# untitled.net
KiCad netlist of a schematic drawn in EAGLE
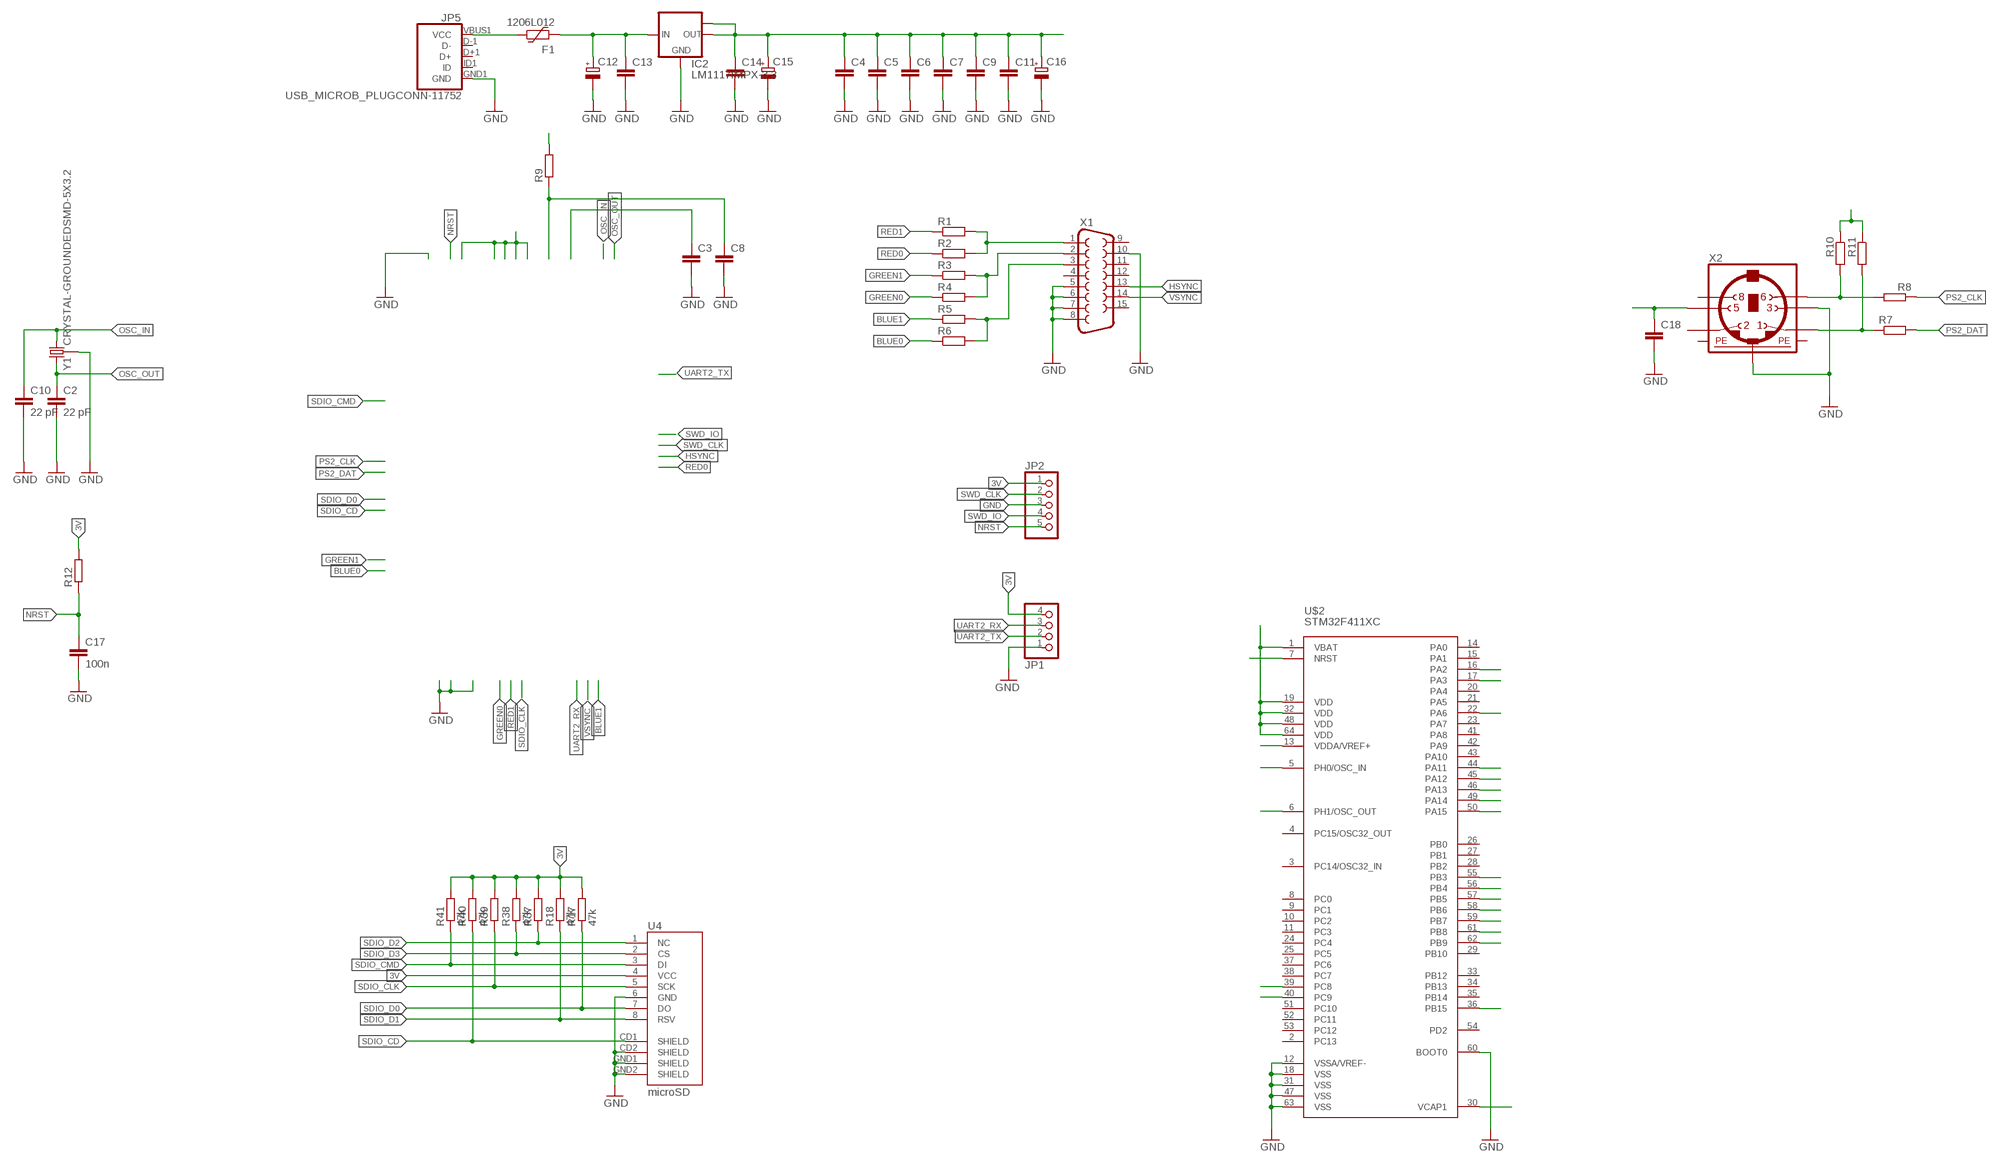
[diagram p0: schematic, sheet 1]

(export (version "E")
  (design (tool "Eeschema 10.0.6"))
  (components
    (comp (ref "C2")
      (value "22 pF")
      (footprint "eagle-import:C0603")
      (libsource (lib "eagle-import") (part "C-EUC0603"))
    )
    (comp (ref "C3")
      (value "C-EUC0603")
      (footprint "eagle-import:C0603")
      (libsource (lib "eagle-import") (part "C-EUC0603"))
    )
    (comp (ref "C4")
      (value "C-EUC0603")
      (footprint "eagle-import:C0603")
      (libsource (lib "eagle-import") (part "C-EUC0603"))
    )
    (comp (ref "C5")
      (value "C-EUC0603")
      (footprint "eagle-import:C0603")
      (libsource (lib "eagle-import") (part "C-EUC0603"))
    )
    (comp (ref "C6")
      (value "C-EUC0603")
      (footprint "eagle-import:C0603")
      (libsource (lib "eagle-import") (part "C-EUC0603"))
    )
    (comp (ref "C7")
      (value "C-EUC0603")
      (footprint "eagle-import:C0603")
      (libsource (lib "eagle-import") (part "C-EUC0603"))
    )
    (comp (ref "C8")
      (value "C-EUC0603")
      (footprint "eagle-import:C0603")
      (libsource (lib "eagle-import") (part "C-EUC0603"))
    )
    (comp (ref "C9")
      (value "C-EUC0603")
      (footprint "eagle-import:C0603")
      (libsource (lib "eagle-import") (part "C-EUC0603"))
    )
    (comp (ref "C10")
      (value "22 pF")
      (footprint "eagle-import:C0603")
      (libsource (lib "eagle-import") (part "C-EUC0603"))
    )
    (comp (ref "C11")
      (value "C-EUC0603")
      (footprint "eagle-import:C0603")
      (libsource (lib "eagle-import") (part "C-EUC0603"))
    )
    (comp (ref "C12")
      (value "CPOL-EUSMCB")
      (footprint "eagle-import:SMC_B")
      (libsource (lib "eagle-import") (part "CPOL-EUSMCB"))
    )
    (comp (ref "C13")
      (value "C-EUC0603")
      (footprint "eagle-import:C0603")
      (libsource (lib "eagle-import") (part "C-EUC0603"))
    )
    (comp (ref "C14")
      (value "C-EUC0603")
      (footprint "eagle-import:C0603")
      (libsource (lib "eagle-import") (part "C-EUC0603"))
    )
    (comp (ref "C15")
      (value "CPOL-EUSMCB")
      (footprint "eagle-import:SMC_B")
      (libsource (lib "eagle-import") (part "CPOL-EUSMCB"))
    )
    (comp (ref "C16")
      (value "CPOL-EUSMCB")
      (footprint "eagle-import:SMC_B")
      (libsource (lib "eagle-import") (part "CPOL-EUSMCB"))
    )
    (comp (ref "C17")
      (value "100n")
      (footprint "eagle-import:C0603")
      (libsource (lib "eagle-import") (part "C-EUC0603"))
    )
    (comp (ref "C18")
      (value "C-EUC0603")
      (footprint "eagle-import:C0603")
      (libsource (lib "eagle-import") (part "C-EUC0603"))
    )
    (comp (ref "F1")
      (value "1206L012")
      (footprint "eagle-import:1206L")
      (fields (field (name "MF") "Littelfuse"))
      (libsource (lib "eagle-import") (part "?1206L012"))
    )
    (comp (ref "IC2")
      (value "LM1117IMPX-3.3")
      (footprint "eagle-import:SOT223")
      (libsource (lib "eagle-import") (part "LM1117IMPX-3.3"))
    )
    (comp (ref "JP1")
      (value "PINHD-1X4")
      (footprint "eagle-import:1X04")
      (libsource (lib "eagle-import") (part "PINHD-1X4"))
    )
    (comp (ref "JP2")
      (value "PINHD-1X5")
      (footprint "eagle-import:1X05")
      (libsource (lib "eagle-import") (part "PINHD-1X5"))
    )
    (comp (ref "JP5")
      (value "USB_MICROB_PLUGCONN-11752")
      (footprint "eagle-import:USB-B-MICRO-SMD_V03")
      (libsource (lib "eagle-import") (part "USB_MICROB_PLUGCONN-11752"))
    )
    (comp (ref "R1")
      (value "R-EU_R0603")
      (footprint "eagle-import:R0603")
      (libsource (lib "eagle-import") (part "R-EU_R0603"))
    )
    (comp (ref "R2")
      (value "R-EU_R0603")
      (footprint "eagle-import:R0603")
      (libsource (lib "eagle-import") (part "R-EU_R0603"))
    )
    (comp (ref "R3")
      (value "R-EU_R0603")
      (footprint "eagle-import:R0603")
      (libsource (lib "eagle-import") (part "R-EU_R0603"))
    )
    (comp (ref "R4")
      (value "R-EU_R0603")
      (footprint "eagle-import:R0603")
      (libsource (lib "eagle-import") (part "R-EU_R0603"))
    )
    (comp (ref "R5")
      (value "R-EU_R0603")
      (footprint "eagle-import:R0603")
      (libsource (lib "eagle-import") (part "R-EU_R0603"))
    )
    (comp (ref "R6")
      (value "R-EU_R0603")
      (footprint "eagle-import:R0603")
      (libsource (lib "eagle-import") (part "R-EU_R0603"))
    )
    (comp (ref "R7")
      (value "R-EU_R0603")
      (footprint "eagle-import:R0603")
      (libsource (lib "eagle-import") (part "R-EU_R0603"))
    )
    (comp (ref "R8")
      (value "R-EU_R0603")
      (footprint "eagle-import:R0603")
      (libsource (lib "eagle-import") (part "R-EU_R0603"))
    )
    (comp (ref "R9")
      (value "R-EU_M0805")
      (footprint "eagle-import:M0805")
      (libsource (lib "eagle-import") (part "R-EU_M0805"))
    )
    (comp (ref "R10")
      (value "R-EU_R0603")
      (footprint "eagle-import:R0603")
      (libsource (lib "eagle-import") (part "R-EU_R0603"))
    )
    (comp (ref "R11")
      (value "R-EU_R0603")
      (footprint "eagle-import:R0603")
      (libsource (lib "eagle-import") (part "R-EU_R0603"))
    )
    (comp (ref "R12")
      (value "R-EU_R0603")
      (footprint "eagle-import:R0603")
      (libsource (lib "eagle-import") (part "R-EU_R0603"))
    )
    (comp (ref "R17")
      (value "47k")
      (footprint "eagle-import:R0603")
      (libsource (lib "eagle-import") (part "R-EU_R0603"))
    )
    (comp (ref "R18")
      (value "47k")
      (footprint "eagle-import:R0603")
      (libsource (lib "eagle-import") (part "R-EU_R0603"))
    )
    (comp (ref "R37")
      (value "R-EU_R0402")
      (footprint "eagle-import:R0402")
      (libsource (lib "eagle-import") (part "R-EU_R0402"))
    )
    (comp (ref "R38")
      (value "47k")
      (footprint "eagle-import:R0402")
      (libsource (lib "eagle-import") (part "R-EU_R0402"))
    )
    (comp (ref "R39")
      (value "R-EU_R0603")
      (footprint "eagle-import:R0603")
      (libsource (lib "eagle-import") (part "R-EU_R0603"))
    )
    (comp (ref "R40")
      (value "47k")
      (footprint "eagle-import:R0603")
      (libsource (lib "eagle-import") (part "R-EU_R0603"))
    )
    (comp (ref "R41")
      (value "47k")
      (footprint "eagle-import:R0402")
      (libsource (lib "eagle-import") (part "R-EU_R0402"))
    )
    (comp (ref "U$2")
      (value "STM32F411XC")
      (footprint "eagle-import:LQFP64")
      (libsource (lib "eagle-import") (part "STM32F411XC"))
    )
    (comp (ref "U4")
      (value "microSD")
      (footprint "eagle-import:USD-SOCKET-PP")
      (libsource (lib "eagle-import") (part "USD-SOCKETUSD"))
    )
    (comp (ref "X1")
      (value "F15HDH")
      (footprint "eagle-import:HDF15H")
      (libsource (lib "eagle-import") (part "F15HDH"))
    )
    (comp (ref "X2")
      (value "MINI_DIN_6")
      (footprint "eagle-import:M_DIN6")
      (libsource (lib "eagle-import") (part "MINI_DIN_6"))
    )
    (comp (ref "Y1")
      (value "CRYSTAL-GROUNDEDSMD-5X3.2")
      (footprint "eagle-import:CRYSTAL-SMD-5X3.2-4PAD")
      (libsource (lib "eagle-import") (part "CRYSTAL-GROUNDEDSMD-5X3.2"))
    )
  )
  (nets
    (net (code "1") (name "/5V") (class "Default")
      (node (ref "C12") (pin "+") (pinfunction "+_+") (pintype "passive"))
      (node (ref "C13") (pin "1") (pinfunction "1_1") (pintype "passive"))
      (node (ref "C18") (pin "1") (pinfunction "1_1") (pintype "passive"))
      (node (ref "F1") (pin "2") (pinfunction "2_2") (pintype "passive"))
      (node (ref "IC2") (pin "3") (pinfunction "IN_3") (pintype "input"))
      (node (ref "X2") (pin "5") (pinfunction "5_5") (pintype "passive"))
    )
    (net (code "2") (name "/N$6") (class "Default")
      (node (ref "C8") (pin "1") (pinfunction "1_1") (pintype "passive"))
      (node (ref "R9") (pin "1") (pinfunction "1_1") (pintype "passive"))
      (node (ref "U$2") (pin "13") (pinfunction "VDDA/VREF+_13") (pintype "bidirectional"))
    )
    (net (code "3") (name "/N$8") (class "Default")
      (node (ref "C3") (pin "1") (pinfunction "1_1") (pintype "passive"))
      (node (ref "U$2") (pin "30") (pinfunction "VCAP1_30") (pintype "bidirectional"))
    )
    (net (code "4") (name "/PE1") (class "Default")
      (node (ref "X2") (pin "SH1") (pinfunction "PE1_SH1") (pintype "power_in"))
    )
    (net (code "5") (name "/PE3") (class "Default")
      (node (ref "X2") (pin "SH3") (pinfunction "PE3_SH3") (pintype "power_in"))
    )
    (net (code "6") (name "3V") (class "Default")
      (node (ref "C11") (pin "1") (pinfunction "1_1") (pintype "passive"))
      (node (ref "C14") (pin "1") (pinfunction "1_1") (pintype "passive"))
      (node (ref "C15") (pin "+") (pinfunction "+_+") (pintype "passive"))
      (node (ref "C16") (pin "+") (pinfunction "+_+") (pintype "passive"))
      (node (ref "C4") (pin "1") (pinfunction "1_1") (pintype "passive"))
      (node (ref "C5") (pin "1") (pinfunction "1_1") (pintype "passive"))
      (node (ref "C6") (pin "1") (pinfunction "1_1") (pintype "passive"))
      (node (ref "C7") (pin "1") (pinfunction "1_1") (pintype "passive"))
      (node (ref "C9") (pin "1") (pinfunction "1_1") (pintype "passive"))
      (node (ref "IC2") (pin "2") (pinfunction "OUT_2") (pintype "passive"))
      (node (ref "IC2") (pin "TAB") (pinfunction "OUT1_TAB") (pintype "passive"))
      (node (ref "JP1") (pin "4") (pinfunction "4_4") (pintype "passive"))
      (node (ref "JP2") (pin "1") (pinfunction "1_1") (pintype "passive"))
      (node (ref "R10") (pin "1") (pinfunction "1_1") (pintype "passive"))
      (node (ref "R11") (pin "1") (pinfunction "1_1") (pintype "passive"))
      (node (ref "R12") (pin "2") (pinfunction "2_2") (pintype "passive"))
      (node (ref "R17") (pin "2") (pinfunction "2_2") (pintype "passive"))
      (node (ref "R18") (pin "2") (pinfunction "2_2") (pintype "passive"))
      (node (ref "R37") (pin "2") (pinfunction "2_2") (pintype "passive"))
      (node (ref "R38") (pin "2") (pinfunction "2_2") (pintype "passive"))
      (node (ref "R39") (pin "2") (pinfunction "2_2") (pintype "passive"))
      (node (ref "R40") (pin "2") (pinfunction "2_2") (pintype "passive"))
      (node (ref "R41") (pin "2") (pinfunction "2_2") (pintype "passive"))
      (node (ref "R9") (pin "2") (pinfunction "2_2") (pintype "passive"))
      (node (ref "U$2") (pin "1") (pinfunction "VBAT_1") (pintype "bidirectional"))
      (node (ref "U$2") (pin "19") (pinfunction "VDD_19") (pintype "bidirectional"))
      (node (ref "U$2") (pin "32") (pinfunction "VDD_32") (pintype "bidirectional"))
      (node (ref "U$2") (pin "48") (pinfunction "VDD_48") (pintype "bidirectional"))
      (node (ref "U$2") (pin "64") (pinfunction "VDD_64") (pintype "bidirectional"))
      (node (ref "U4") (pin "4") (pinfunction "VCC_4") (pintype "bidirectional"))
    )
    (net (code "7") (name "BLUE0") (class "Default")
      (node (ref "R6") (pin "1") (pinfunction "1_1") (pintype "passive"))
      (node (ref "U$2") (pin "59") (pinfunction "PB7_59") (pintype "bidirectional"))
    )
    (net (code "8") (name "BLUE1") (class "Default")
      (node (ref "R5") (pin "1") (pinfunction "1_1") (pintype "passive"))
      (node (ref "U$2") (pin "61") (pinfunction "PB8_61") (pintype "bidirectional"))
    )
    (net (code "9") (name "GND") (class "Default")
      (node (ref "C10") (pin "2") (pinfunction "2_2") (pintype "passive"))
      (node (ref "C11") (pin "2") (pinfunction "2_2") (pintype "passive"))
      (node (ref "C12") (pin "-") (pinfunction "-_-") (pintype "passive"))
      (node (ref "C13") (pin "2") (pinfunction "2_2") (pintype "passive"))
      (node (ref "C14") (pin "2") (pinfunction "2_2") (pintype "passive"))
      (node (ref "C15") (pin "-") (pinfunction "-_-") (pintype "passive"))
      (node (ref "C16") (pin "-") (pinfunction "-_-") (pintype "passive"))
      (node (ref "C17") (pin "2") (pinfunction "2_2") (pintype "passive"))
      (node (ref "C18") (pin "2") (pinfunction "2_2") (pintype "passive"))
      (node (ref "C2") (pin "2") (pinfunction "2_2") (pintype "passive"))
      (node (ref "C3") (pin "2") (pinfunction "2_2") (pintype "passive"))
      (node (ref "C4") (pin "2") (pinfunction "2_2") (pintype "passive"))
      (node (ref "C5") (pin "2") (pinfunction "2_2") (pintype "passive"))
      (node (ref "C6") (pin "2") (pinfunction "2_2") (pintype "passive"))
      (node (ref "C7") (pin "2") (pinfunction "2_2") (pintype "passive"))
      (node (ref "C8") (pin "2") (pinfunction "2_2") (pintype "passive"))
      (node (ref "C9") (pin "2") (pinfunction "2_2") (pintype "passive"))
      (node (ref "IC2") (pin "1") (pinfunction "GND_1") (pintype "input"))
      (node (ref "JP1") (pin "1") (pinfunction "1_1") (pintype "passive"))
      (node (ref "JP2") (pin "3") (pinfunction "3_3") (pintype "passive"))
      (node (ref "JP5") (pin "GND1") (pinfunction "GND_GND1") (pintype "bidirectional"))
      (node (ref "U$2") (pin "12") (pinfunction "VSSA/VREF-_12") (pintype "bidirectional"))
      (node (ref "U$2") (pin "18") (pinfunction "VSS_18") (pintype "bidirectional"))
      (node (ref "U$2") (pin "31") (pinfunction "VSS_31") (pintype "bidirectional"))
      (node (ref "U$2") (pin "47") (pinfunction "VSS_47") (pintype "bidirectional"))
      (node (ref "U$2") (pin "60") (pinfunction "BOOT0_60") (pintype "bidirectional"))
      (node (ref "U$2") (pin "63") (pinfunction "VSS_63") (pintype "bidirectional"))
      (node (ref "U4") (pin "6") (pinfunction "GND_6") (pintype "bidirectional"))
      (node (ref "U4") (pin "CD2") (pinfunction "SHIELD_CD2") (pintype "bidirectional"))
      (node (ref "U4") (pin "GND1") (pinfunction "SHIELD_GND1") (pintype "bidirectional"))
      (node (ref "U4") (pin "GND2") (pinfunction "SHIELD_GND2") (pintype "bidirectional"))
      (node (ref "X1") (pin "10") (pinfunction "10_10") (pintype "passive"))
      (node (ref "X1") (pin "5") (pinfunction "5_5") (pintype "passive"))
      (node (ref "X1") (pin "6") (pinfunction "6_6") (pintype "passive"))
      (node (ref "X1") (pin "7") (pinfunction "7_7") (pintype "passive"))
      (node (ref "X1") (pin "8") (pinfunction "8_8") (pintype "passive"))
      (node (ref "X2") (pin "3") (pinfunction "3_3") (pintype "passive"))
      (node (ref "X2") (pin "SH2") (pinfunction "PE2_SH2") (pintype "power_in"))
      (node (ref "Y1") (pin "2") (pinfunction "3_2") (pintype "passive"))
      (node (ref "Y1") (pin "4") (pinfunction "3_4") (pintype "passive"))
    )
    (net (code "10") (name "GREEN0") (class "Default")
      (node (ref "R4") (pin "1") (pinfunction "1_1") (pintype "passive"))
      (node (ref "U$2") (pin "57") (pinfunction "PB5_57") (pintype "bidirectional"))
    )
    (net (code "11") (name "GREEN1") (class "Default")
      (node (ref "R3") (pin "1") (pinfunction "1_1") (pintype "passive"))
      (node (ref "U$2") (pin "58") (pinfunction "PB6_58") (pintype "bidirectional"))
    )
    (net (code "12") (name "HSYNC") (class "Default")
      (node (ref "U$2") (pin "50") (pinfunction "PA15_50") (pintype "bidirectional"))
      (node (ref "X1") (pin "13") (pinfunction "13_13") (pintype "passive"))
    )
    (net (code "13") (name "NRST") (class "Default")
      (node (ref "C17") (pin "1") (pinfunction "1_1") (pintype "passive"))
      (node (ref "JP2") (pin "5") (pinfunction "5_5") (pintype "passive"))
      (node (ref "R12") (pin "1") (pinfunction "1_1") (pintype "passive"))
      (node (ref "U$2") (pin "7") (pinfunction "NRST_7") (pintype "bidirectional"))
    )
    (net (code "14") (name "Net-(JP5-VCC)") (class "Default")
      (node (ref "F1") (pin "1") (pinfunction "1_1") (pintype "passive"))
      (node (ref "JP5") (pin "VBUS1") (pinfunction "VCC_VBUS1") (pintype "bidirectional"))
    )
    (net (code "15") (name "Net-(R1-Pad2)") (class "Default")
      (node (ref "R1") (pin "2") (pinfunction "2_2") (pintype "passive"))
      (node (ref "R2") (pin "2") (pinfunction "2_2") (pintype "passive"))
      (node (ref "X1") (pin "1") (pinfunction "1_1") (pintype "passive"))
    )
    (net (code "16") (name "Net-(R3-Pad2)") (class "Default")
      (node (ref "R3") (pin "2") (pinfunction "2_2") (pintype "passive"))
      (node (ref "R4") (pin "2") (pinfunction "2_2") (pintype "passive"))
      (node (ref "X1") (pin "2") (pinfunction "2_2") (pintype "passive"))
    )
    (net (code "17") (name "Net-(R5-Pad2)") (class "Default")
      (node (ref "R5") (pin "2") (pinfunction "2_2") (pintype "passive"))
      (node (ref "R6") (pin "2") (pinfunction "2_2") (pintype "passive"))
      (node (ref "X1") (pin "3") (pinfunction "3_3") (pintype "passive"))
    )
    (net (code "18") (name "Net-(R10-Pad2)") (class "Default")
      (node (ref "R10") (pin "2") (pinfunction "2_2") (pintype "passive"))
      (node (ref "R8") (pin "2") (pinfunction "2_2") (pintype "passive"))
      (node (ref "X2") (pin "6") (pinfunction "6_6") (pintype "passive"))
    )
    (net (code "19") (name "Net-(R11-Pad2)") (class "Default")
      (node (ref "R11") (pin "2") (pinfunction "2_2") (pintype "passive"))
      (node (ref "R7") (pin "1") (pinfunction "1_1") (pintype "passive"))
      (node (ref "X2") (pin "1") (pinfunction "1_1") (pintype "passive"))
    )
    (net (code "20") (name "OSC_IN") (class "Default")
      (node (ref "C10") (pin "1") (pinfunction "1_1") (pintype "passive"))
      (node (ref "U$2") (pin "5") (pinfunction "PH0/OSC_IN_5") (pintype "bidirectional"))
      (node (ref "Y1") (pin "1") (pinfunction "2_1") (pintype "passive"))
    )
    (net (code "21") (name "OSC_OUT") (class "Default")
      (node (ref "C2") (pin "1") (pinfunction "1_1") (pintype "passive"))
      (node (ref "U$2") (pin "6") (pinfunction "PH1/OSC_OUT_6") (pintype "bidirectional"))
      (node (ref "Y1") (pin "3") (pinfunction "1_3") (pintype "passive"))
    )
    (net (code "22") (name "PS2_CLK") (class "Default")
      (node (ref "R8") (pin "1") (pinfunction "1_1") (pintype "passive"))
      (node (ref "U$2") (pin "44") (pinfunction "PA11_44") (pintype "bidirectional"))
    )
    (net (code "23") (name "PS2_DAT") (class "Default")
      (node (ref "R7") (pin "2") (pinfunction "2_2") (pintype "passive"))
      (node (ref "U$2") (pin "45") (pinfunction "PA12_45") (pintype "bidirectional"))
    )
    (net (code "24") (name "RED0") (class "Default")
      (node (ref "R2") (pin "1") (pinfunction "1_1") (pintype "passive"))
      (node (ref "U$2") (pin "55") (pinfunction "PB3_55") (pintype "bidirectional"))
    )
    (net (code "25") (name "RED1") (class "Default")
      (node (ref "R1") (pin "1") (pinfunction "1_1") (pintype "passive"))
      (node (ref "U$2") (pin "56") (pinfunction "PB4_56") (pintype "bidirectional"))
    )
    (net (code "26") (name "SDIO_CD") (class "Default")
      (node (ref "R40") (pin "1") (pinfunction "1_1") (pintype "passive"))
      (node (ref "U$2") (pin "40") (pinfunction "PC9_40") (pintype "bidirectional"))
      (node (ref "U4") (pin "CD1") (pinfunction "SHIELD_CD1") (pintype "bidirectional"))
    )
    (net (code "27") (name "SDIO_CLK") (class "Default")
      (node (ref "R39") (pin "1") (pinfunction "1_1") (pintype "passive"))
      (node (ref "U$2") (pin "36") (pinfunction "PB15_36") (pintype "bidirectional"))
      (node (ref "U4") (pin "5") (pinfunction "SCK_5") (pintype "bidirectional"))
    )
    (net (code "28") (name "SDIO_CMD") (class "Default")
      (node (ref "R41") (pin "1") (pinfunction "1_1") (pintype "passive"))
      (node (ref "U$2") (pin "22") (pinfunction "PA6_22") (pintype "bidirectional"))
      (node (ref "U4") (pin "3") (pinfunction "DI_3") (pintype "bidirectional"))
    )
    (net (code "29") (name "SDIO_D0") (class "Default")
      (node (ref "R17") (pin "1") (pinfunction "1_1") (pintype "passive"))
      (node (ref "U$2") (pin "39") (pinfunction "PC8_39") (pintype "bidirectional"))
      (node (ref "U4") (pin "7") (pinfunction "DO_7") (pintype "bidirectional"))
    )
    (net (code "30") (name "SDIO_D1") (class "Default")
      (node (ref "R18") (pin "1") (pinfunction "1_1") (pintype "passive"))
      (node (ref "U4") (pin "8") (pinfunction "RSV_8") (pintype "bidirectional"))
    )
    (net (code "31") (name "SDIO_D2") (class "Default")
      (node (ref "R37") (pin "1") (pinfunction "1_1") (pintype "passive"))
      (node (ref "U4") (pin "1") (pinfunction "NC_1") (pintype "bidirectional"))
    )
    (net (code "32") (name "SDIO_D3") (class "Default")
      (node (ref "R38") (pin "1") (pinfunction "1_1") (pintype "passive"))
      (node (ref "U4") (pin "2") (pinfunction "CS_2") (pintype "bidirectional"))
    )
    (net (code "33") (name "SWD_CLK") (class "Default")
      (node (ref "JP2") (pin "2") (pinfunction "2_2") (pintype "passive"))
      (node (ref "U$2") (pin "49") (pinfunction "PA14_49") (pintype "bidirectional"))
    )
    (net (code "34") (name "SWD_IO") (class "Default")
      (node (ref "JP2") (pin "4") (pinfunction "4_4") (pintype "passive"))
      (node (ref "U$2") (pin "46") (pinfunction "PA13_46") (pintype "bidirectional"))
    )
    (net (code "35") (name "UART2_RX") (class "Default")
      (node (ref "JP1") (pin "3") (pinfunction "3_3") (pintype "passive"))
      (node (ref "U$2") (pin "17") (pinfunction "PA3_17") (pintype "bidirectional"))
    )
    (net (code "36") (name "UART2_TX") (class "Default")
      (node (ref "JP1") (pin "2") (pinfunction "2_2") (pintype "passive"))
      (node (ref "U$2") (pin "16") (pinfunction "PA2_16") (pintype "bidirectional"))
    )
    (net (code "37") (name "VSYNC") (class "Default")
      (node (ref "U$2") (pin "62") (pinfunction "PB9_62") (pintype "bidirectional"))
      (node (ref "X1") (pin "14") (pinfunction "14_14") (pintype "passive"))
    )
    (net (code "38") (name "unconnected-(JP5-D+-PadD+1)") (class "Default")
      (node (ref "JP5") (pin "D+1") (pinfunction "D+_D+1") (pintype "bidirectional"))
    )
    (net (code "39") (name "unconnected-(JP5-D--PadD-1)") (class "Default")
      (node (ref "JP5") (pin "D-1") (pinfunction "D-_D-1") (pintype "bidirectional"))
    )
    (net (code "40") (name "unconnected-(JP5-ID-PadID1)") (class "Default")
      (node (ref "JP5") (pin "ID1") (pinfunction "ID_ID1") (pintype "bidirectional"))
    )
    (net (code "41") (name "unconnected-(U$2-PA0-Pad14)") (class "Default")
      (node (ref "U$2") (pin "14") (pinfunction "PA0_14") (pintype "bidirectional"))
    )
    (net (code "42") (name "unconnected-(U$2-PA1-Pad15)") (class "Default")
      (node (ref "U$2") (pin "15") (pinfunction "PA1_15") (pintype "bidirectional"))
    )
    (net (code "43") (name "unconnected-(U$2-PA4-Pad20)") (class "Default")
      (node (ref "U$2") (pin "20") (pinfunction "PA4_20") (pintype "bidirectional"))
    )
    (net (code "44") (name "unconnected-(U$2-PA5-Pad21)") (class "Default")
      (node (ref "U$2") (pin "21") (pinfunction "PA5_21") (pintype "bidirectional"))
    )
    (net (code "45") (name "unconnected-(U$2-PA7-Pad23)") (class "Default")
      (node (ref "U$2") (pin "23") (pinfunction "PA7_23") (pintype "bidirectional"))
    )
    (net (code "46") (name "unconnected-(U$2-PA8-Pad41)") (class "Default")
      (node (ref "U$2") (pin "41") (pinfunction "PA8_41") (pintype "bidirectional"))
    )
    (net (code "47") (name "unconnected-(U$2-PA9-Pad42)") (class "Default")
      (node (ref "U$2") (pin "42") (pinfunction "PA9_42") (pintype "bidirectional"))
    )
    (net (code "48") (name "unconnected-(U$2-PA10-Pad43)") (class "Default")
      (node (ref "U$2") (pin "43") (pinfunction "PA10_43") (pintype "bidirectional"))
    )
    (net (code "49") (name "unconnected-(U$2-PB0-Pad26)") (class "Default")
      (node (ref "U$2") (pin "26") (pinfunction "PB0_26") (pintype "bidirectional"))
    )
    (net (code "50") (name "unconnected-(U$2-PB1-Pad27)") (class "Default")
      (node (ref "U$2") (pin "27") (pinfunction "PB1_27") (pintype "bidirectional"))
    )
    (net (code "51") (name "unconnected-(U$2-PB2-Pad28)") (class "Default")
      (node (ref "U$2") (pin "28") (pinfunction "PB2_28") (pintype "bidirectional"))
    )
    (net (code "52") (name "unconnected-(U$2-PB10-Pad29)") (class "Default")
      (node (ref "U$2") (pin "29") (pinfunction "PB10_29") (pintype "bidirectional"))
    )
    (net (code "53") (name "unconnected-(U$2-PB12-Pad33)") (class "Default")
      (node (ref "U$2") (pin "33") (pinfunction "PB12_33") (pintype "bidirectional"))
    )
    (net (code "54") (name "unconnected-(U$2-PB13-Pad34)") (class "Default")
      (node (ref "U$2") (pin "34") (pinfunction "PB13_34") (pintype "bidirectional"))
    )
    (net (code "55") (name "unconnected-(U$2-PB14-Pad35)") (class "Default")
      (node (ref "U$2") (pin "35") (pinfunction "PB14_35") (pintype "bidirectional"))
    )
    (net (code "56") (name "unconnected-(U$2-PC0-Pad8)") (class "Default")
      (node (ref "U$2") (pin "8") (pinfunction "PC0_8") (pintype "bidirectional"))
    )
    (net (code "57") (name "unconnected-(U$2-PC1-Pad9)") (class "Default")
      (node (ref "U$2") (pin "9") (pinfunction "PC1_9") (pintype "bidirectional"))
    )
    (net (code "58") (name "unconnected-(U$2-PC2-Pad10)") (class "Default")
      (node (ref "U$2") (pin "10") (pinfunction "PC2_10") (pintype "bidirectional"))
    )
    (net (code "59") (name "unconnected-(U$2-PC3-Pad11)") (class "Default")
      (node (ref "U$2") (pin "11") (pinfunction "PC3_11") (pintype "bidirectional"))
    )
    (net (code "60") (name "unconnected-(U$2-PC4-Pad24)") (class "Default")
      (node (ref "U$2") (pin "24") (pinfunction "PC4_24") (pintype "bidirectional"))
    )
    (net (code "61") (name "unconnected-(U$2-PC5-Pad25)") (class "Default")
      (node (ref "U$2") (pin "25") (pinfunction "PC5_25") (pintype "bidirectional"))
    )
    (net (code "62") (name "unconnected-(U$2-PC6-Pad37)") (class "Default")
      (node (ref "U$2") (pin "37") (pinfunction "PC6_37") (pintype "bidirectional"))
    )
    (net (code "63") (name "unconnected-(U$2-PC7-Pad38)") (class "Default")
      (node (ref "U$2") (pin "38") (pinfunction "PC7_38") (pintype "bidirectional"))
    )
    (net (code "64") (name "unconnected-(U$2-PC10-Pad51)") (class "Default")
      (node (ref "U$2") (pin "51") (pinfunction "PC10_51") (pintype "bidirectional"))
    )
    (net (code "65") (name "unconnected-(U$2-PC11-Pad52)") (class "Default")
      (node (ref "U$2") (pin "52") (pinfunction "PC11_52") (pintype "bidirectional"))
    )
    (net (code "66") (name "unconnected-(U$2-PC12-Pad53)") (class "Default")
      (node (ref "U$2") (pin "53") (pinfunction "PC12_53") (pintype "bidirectional"))
    )
    (net (code "67") (name "unconnected-(U$2-PC13-Pad2)") (class "Default")
      (node (ref "U$2") (pin "2") (pinfunction "PC13_2") (pintype "bidirectional"))
    )
    (net (code "68") (name "unconnected-(U$2-PC14{slash}OSC32_IN-Pad3)") (class "Default")
      (node (ref "U$2") (pin "3") (pinfunction "PC14/OSC32_IN_3") (pintype "bidirectional"))
    )
    (net (code "69") (name "unconnected-(U$2-PC15{slash}OSC32_OUT-Pad4)") (class "Default")
      (node (ref "U$2") (pin "4") (pinfunction "PC15/OSC32_OUT_4") (pintype "bidirectional"))
    )
    (net (code "70") (name "unconnected-(U$2-PD2-Pad54)") (class "Default")
      (node (ref "U$2") (pin "54") (pinfunction "PD2_54") (pintype "bidirectional"))
    )
    (net (code "71") (name "unconnected-(X1-Pad4)") (class "Default")
      (node (ref "X1") (pin "4") (pinfunction "4_4") (pintype "passive"))
    )
    (net (code "72") (name "unconnected-(X1-Pad9)") (class "Default")
      (node (ref "X1") (pin "9") (pinfunction "9_9") (pintype "passive"))
    )
    (net (code "73") (name "unconnected-(X1-Pad11)") (class "Default")
      (node (ref "X1") (pin "11") (pinfunction "11_11") (pintype "passive"))
    )
    (net (code "74") (name "unconnected-(X1-Pad12)") (class "Default")
      (node (ref "X1") (pin "12") (pinfunction "12_12") (pintype "passive"))
    )
    (net (code "75") (name "unconnected-(X1-Pad15)") (class "Default")
      (node (ref "X1") (pin "15") (pinfunction "15_15") (pintype "passive"))
    )
    (net (code "76") (name "unconnected-(X2-Pad2)") (class "Default")
      (node (ref "X2") (pin "2") (pinfunction "2_2") (pintype "passive"))
    )
    (net (code "77") (name "unconnected-(X2-Pad8)") (class "Default")
      (node (ref "X2") (pin "8") (pinfunction "8_8") (pintype "passive"))
    )
  )
)
